# Height_Gauge-2-1.net
KiCad netlist of a schematic drawn in EAGLE
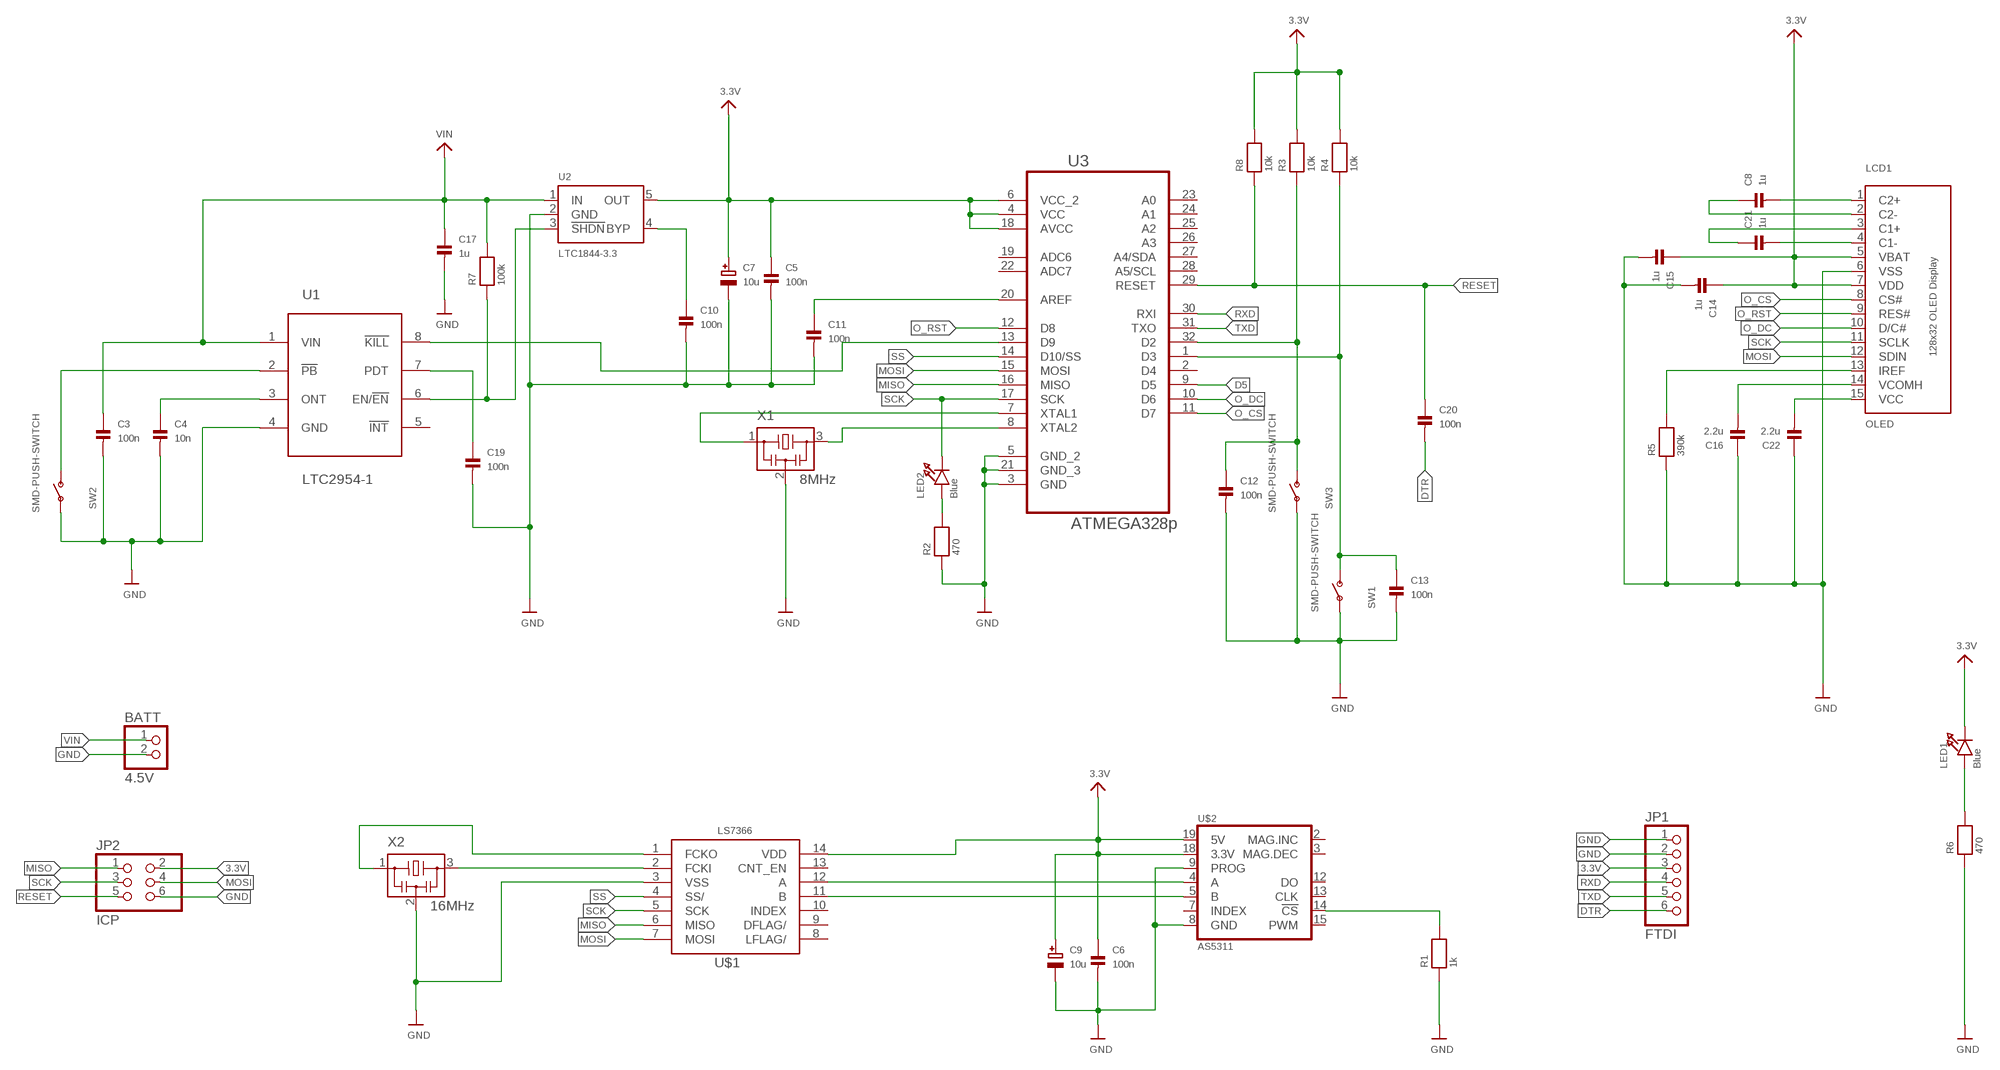
[diagram p0: schematic, sheet 1]

(export (version "E")
  (design (tool "Eeschema 10.0.6"))
  (components
    (comp (ref "BATT")
      (value "4.5V")
      (footprint "eagle-import:1X02")
      (libsource (lib "eagle-import") (part "PINHD-1X2"))
    )
    (comp (ref "C3")
      (value "100n")
      (footprint "eagle-import:0805")
      (libsource (lib "eagle-import") (part "CAP_CERAMIC0805"))
    )
    (comp (ref "C4")
      (value "10n")
      (footprint "eagle-import:0805")
      (libsource (lib "eagle-import") (part "CAP_CERAMIC0805"))
    )
    (comp (ref "C5")
      (value "100n")
      (footprint "eagle-import:0805")
      (libsource (lib "eagle-import") (part "CAP_CERAMIC0805"))
    )
    (comp (ref "C6")
      (value "100n")
      (footprint "eagle-import:0805")
      (libsource (lib "eagle-import") (part "CAP_CERAMIC0805"))
    )
    (comp (ref "C7")
      (value "10u")
      (footprint "eagle-import:EIA3216-18_A-W")
      (libsource (lib "eagle-import") (part "CAP_TANTALUMA/3216_WAVE"))
    )
    (comp (ref "C8")
      (value "1u")
      (footprint "eagle-import:0805")
      (libsource (lib "eagle-import") (part "CAP_CERAMIC0805"))
    )
    (comp (ref "C9")
      (value "10u")
      (footprint "eagle-import:EIA3216-18_A-W")
      (libsource (lib "eagle-import") (part "CAP_TANTALUMA/3216_WAVE"))
    )
    (comp (ref "C10")
      (value "100n")
      (footprint "eagle-import:0805")
      (libsource (lib "eagle-import") (part "CAP_CERAMIC0805"))
    )
    (comp (ref "C11")
      (value "100n")
      (footprint "eagle-import:0805")
      (libsource (lib "eagle-import") (part "CAP_CERAMIC0805"))
    )
    (comp (ref "C12")
      (value "100n")
      (footprint "eagle-import:0805")
      (libsource (lib "eagle-import") (part "CAP_CERAMIC0805"))
    )
    (comp (ref "C13")
      (value "100n")
      (footprint "eagle-import:0805")
      (libsource (lib "eagle-import") (part "CAP_CERAMIC0805"))
    )
    (comp (ref "C14")
      (value "1u")
      (footprint "eagle-import:0805")
      (libsource (lib "eagle-import") (part "CAP_CERAMIC0805"))
    )
    (comp (ref "C15")
      (value "1u")
      (footprint "eagle-import:0805")
      (libsource (lib "eagle-import") (part "CAP_CERAMIC0805"))
    )
    (comp (ref "C16")
      (value "2.2u")
      (footprint "eagle-import:0805")
      (libsource (lib "eagle-import") (part "CAP_CERAMIC0805"))
    )
    (comp (ref "C17")
      (value "1u")
      (footprint "eagle-import:0805")
      (libsource (lib "eagle-import") (part "CAP_CERAMIC0805"))
    )
    (comp (ref "C19")
      (value "100n")
      (footprint "eagle-import:0805")
      (libsource (lib "eagle-import") (part "CAP_CERAMIC0805"))
    )
    (comp (ref "C20")
      (value "100n")
      (footprint "eagle-import:0805")
      (libsource (lib "eagle-import") (part "CAP_CERAMIC0805"))
    )
    (comp (ref "C21")
      (value "1u")
      (footprint "eagle-import:0805")
      (libsource (lib "eagle-import") (part "CAP_CERAMIC0805"))
    )
    (comp (ref "C22")
      (value "2.2u")
      (footprint "eagle-import:0805")
      (libsource (lib "eagle-import") (part "CAP_CERAMIC0805"))
    )
    (comp (ref "JP1")
      (value "FTDI")
      (footprint "eagle-import:1X06-BIG")
      (libsource (lib "eagle-import") (part "PINHD-1X6B"))
    )
    (comp (ref "JP2")
      (value "ICP")
      (footprint "eagle-import:2X03")
      (libsource (lib "eagle-import") (part "PINHD-2X3"))
    )
    (comp (ref "LCD1")
      (value "OLED")
      (footprint "eagle-import:UG-2832HSWEG04_WRAPAROUND")
      (libsource (lib "eagle-import") (part "DISP_OLED_UG-2832HSWEG04WRAPAROUND"))
    )
    (comp (ref "LED1")
      (value "Blue")
      (footprint "eagle-import:CHIPLED_0805")
      (libsource (lib "eagle-import") (part "LED0805"))
    )
    (comp (ref "LED2")
      (value "Blue")
      (footprint "eagle-import:CHIPLED_0805")
      (libsource (lib "eagle-import") (part "LED0805"))
    )
    (comp (ref "R1")
      (value "1k")
      (footprint "eagle-import:0805")
      (libsource (lib "eagle-import") (part "RESISTOR0805"))
    )
    (comp (ref "R2")
      (value "470")
      (footprint "eagle-import:0805")
      (libsource (lib "eagle-import") (part "RESISTOR0805"))
    )
    (comp (ref "R3")
      (value "10k")
      (footprint "eagle-import:0805")
      (libsource (lib "eagle-import") (part "RESISTOR0805"))
    )
    (comp (ref "R4")
      (value "10k")
      (footprint "eagle-import:0805")
      (libsource (lib "eagle-import") (part "RESISTOR0805"))
    )
    (comp (ref "R5")
      (value "390k")
      (footprint "eagle-import:0805")
      (libsource (lib "eagle-import") (part "RESISTOR0805"))
    )
    (comp (ref "R6")
      (value "470")
      (footprint "eagle-import:0805")
      (libsource (lib "eagle-import") (part "RESISTOR0805"))
    )
    (comp (ref "R7")
      (value "100k")
      (footprint "eagle-import:0805")
      (libsource (lib "eagle-import") (part "RESISTOR0805"))
    )
    (comp (ref "R8")
      (value "10k")
      (footprint "eagle-import:0805")
      (libsource (lib "eagle-import") (part "RESISTOR0805"))
    )
    (comp (ref "SW1")
      (value "SMD-PUSH-SWITCH")
      (footprint "eagle-import:PUSH-BUTTON-SMD")
      (libsource (lib "eagle-import") (part "SMD-PUSH-SWITCH"))
    )
    (comp (ref "SW2")
      (value "SMD-PUSH-SWITCH")
      (footprint "eagle-import:PUSH-BUTTON-SMD")
      (libsource (lib "eagle-import") (part "SMD-PUSH-SWITCH"))
    )
    (comp (ref "SW3")
      (value "SMD-PUSH-SWITCH")
      (footprint "eagle-import:PUSH-BUTTON-SMD")
      (libsource (lib "eagle-import") (part "SMD-PUSH-SWITCH"))
    )
    (comp (ref "U$1")
      (value "LS7366")
      (footprint "eagle-import:SO14")
      (libsource (lib "eagle-import") (part "LS7366"))
    )
    (comp (ref "U$2")
      (value "AS5311")
      (footprint "eagle-import:TSSOP.20")
      (libsource (lib "eagle-import") (part "AS5311"))
    )
    (comp (ref "U1")
      (value "LTC2954-1")
      (footprint "eagle-import:TSOT23-8")
      (libsource (lib "eagle-import") (part "LTC2954"))
    )
    (comp (ref "U2")
      (value "LTC1844-3.3")
      (footprint "eagle-import:TSOT23-5")
      (libsource (lib "eagle-import") (part "LTC1844"))
    )
    (comp (ref "U3")
      (value "ATMEGA328p")
      (footprint "eagle-import:TQFP-32")
      (libsource (lib "eagle-import") (part "ATMEGA328P-AU"))
    )
    (comp (ref "X1")
      (value "8MHz")
      (footprint "eagle-import:CSTCE-CRYSTAL-OSC")
      (libsource (lib "eagle-import") (part "CSTCE-CRYSTAL-OSC"))
    )
    (comp (ref "X2")
      (value "16MHz")
      (footprint "eagle-import:CSTCE-CRYSTAL-OSC")
      (libsource (lib "eagle-import") (part "CSTCE-CRYSTAL-OSC"))
    )
  )
  (nets
    (net (code "1") (name "3.3V") (class "Default")
      (node (ref "C14") (pin "1") (pinfunction "P$1_1") (pintype "passive"))
      (node (ref "C15") (pin "1") (pinfunction "P$1_1") (pintype "passive"))
      (node (ref "C5") (pin "1") (pinfunction "P$1_1") (pintype "passive"))
      (node (ref "C6") (pin "1") (pinfunction "P$1_1") (pintype "passive"))
      (node (ref "C7") (pin "+") (pinfunction "+_+") (pintype "passive"))
      (node (ref "C9") (pin "+") (pinfunction "+_+") (pintype "passive"))
      (node (ref "JP1") (pin "3") (pinfunction "3_3") (pintype "passive"))
      (node (ref "JP2") (pin "2") (pinfunction "2_2") (pintype "passive"))
      (node (ref "LCD1") (pin "5") (pinfunction "VBAT_5") (pintype "bidirectional"))
      (node (ref "LCD1") (pin "7") (pinfunction "VDD_7") (pintype "bidirectional"))
      (node (ref "LED1") (pin "C") (pinfunction "C_C") (pintype "passive"))
      (node (ref "R3") (pin "2") (pinfunction "2_2") (pintype "passive"))
      (node (ref "R4") (pin "2") (pinfunction "2_2") (pintype "passive"))
      (node (ref "R8") (pin "2") (pinfunction "2_2") (pintype "passive"))
      (node (ref "U$1") (pin "14") (pinfunction "VDD_14") (pintype "power_in"))
      (node (ref "U$2") (pin "18") (pinfunction "3.3V_18") (pintype "bidirectional"))
      (node (ref "U$2") (pin "19") (pinfunction "5V_19") (pintype "bidirectional"))
      (node (ref "U2") (pin "5") (pinfunction "OUT_5") (pintype "bidirectional"))
      (node (ref "U3") (pin "18") (pinfunction "AVCC_18") (pintype "power_in"))
      (node (ref "U3") (pin "4") (pinfunction "VCC_4") (pintype "power_in"))
      (node (ref "U3") (pin "6") (pinfunction "VCC_2_6") (pintype "power_in"))
    )
    (net (code "2") (name "D5") (class "Default")
      (node (ref "U3") (pin "9") (pinfunction "D5_9") (pintype "bidirectional"))
    )
    (net (code "3") (name "DTR") (class "Default")
      (node (ref "C20") (pin "2") (pinfunction "P$2_2") (pintype "passive"))
      (node (ref "JP1") (pin "6") (pinfunction "6_6") (pintype "passive"))
    )
    (net (code "4") (name "GND") (class "Default")
      (node (ref "BATT") (pin "2") (pinfunction "2_2") (pintype "passive"))
      (node (ref "C10") (pin "2") (pinfunction "P$2_2") (pintype "passive"))
      (node (ref "C11") (pin "2") (pinfunction "P$2_2") (pintype "passive"))
      (node (ref "C12") (pin "2") (pinfunction "P$2_2") (pintype "passive"))
      (node (ref "C13") (pin "2") (pinfunction "P$2_2") (pintype "passive"))
      (node (ref "C14") (pin "2") (pinfunction "P$2_2") (pintype "passive"))
      (node (ref "C15") (pin "2") (pinfunction "P$2_2") (pintype "passive"))
      (node (ref "C16") (pin "1") (pinfunction "P$1_1") (pintype "passive"))
      (node (ref "C17") (pin "2") (pinfunction "P$2_2") (pintype "passive"))
      (node (ref "C19") (pin "2") (pinfunction "P$2_2") (pintype "passive"))
      (node (ref "C22") (pin "1") (pinfunction "P$1_1") (pintype "passive"))
      (node (ref "C3") (pin "2") (pinfunction "P$2_2") (pintype "passive"))
      (node (ref "C4") (pin "2") (pinfunction "P$2_2") (pintype "passive"))
      (node (ref "C5") (pin "2") (pinfunction "P$2_2") (pintype "passive"))
      (node (ref "C6") (pin "2") (pinfunction "P$2_2") (pintype "passive"))
      (node (ref "C7") (pin "-") (pinfunction "-_-") (pintype "passive"))
      (node (ref "C9") (pin "-") (pinfunction "-_-") (pintype "passive"))
      (node (ref "JP1") (pin "1") (pinfunction "1_1") (pintype "passive"))
      (node (ref "JP1") (pin "2") (pinfunction "2_2") (pintype "passive"))
      (node (ref "JP2") (pin "6") (pinfunction "6_6") (pintype "passive"))
      (node (ref "LCD1") (pin "6") (pinfunction "VSS_6") (pintype "bidirectional"))
      (node (ref "R1") (pin "1") (pinfunction "1_1") (pintype "passive"))
      (node (ref "R2") (pin "1") (pinfunction "1_1") (pintype "passive"))
      (node (ref "R5") (pin "1") (pinfunction "1_1") (pintype "passive"))
      (node (ref "R6") (pin "1") (pinfunction "1_1") (pintype "passive"))
      (node (ref "SW1") (pin "P$1") (pinfunction "P_P$1") (pintype "passive"))
      (node (ref "SW2") (pin "P$1") (pinfunction "P_P$1") (pintype "passive"))
      (node (ref "SW3") (pin "P$1") (pinfunction "P_P$1") (pintype "passive"))
      (node (ref "U$1") (pin "3") (pinfunction "VSS_3") (pintype "power_in"))
      (node (ref "U$2") (pin "8") (pinfunction "GND_8") (pintype "bidirectional"))
      (node (ref "U$2") (pin "9") (pinfunction "PROG_9") (pintype "bidirectional"))
      (node (ref "U1") (pin "4") (pinfunction "GND_4") (pintype "bidirectional"))
      (node (ref "U2") (pin "2") (pinfunction "GND_2") (pintype "bidirectional"))
      (node (ref "U3") (pin "21") (pinfunction "GND_3_21") (pintype "passive"))
      (node (ref "U3") (pin "3") (pinfunction "GND_3") (pintype "passive"))
      (node (ref "U3") (pin "5") (pinfunction "GND_2_5") (pintype "passive"))
      (node (ref "X1") (pin "2") (pinfunction "2_2") (pintype "passive"))
      (node (ref "X2") (pin "2") (pinfunction "2_2") (pintype "passive"))
    )
    (net (code "5") (name "MISO") (class "Default")
      (node (ref "JP2") (pin "1") (pinfunction "1_1") (pintype "passive"))
      (node (ref "U$1") (pin "6") (pinfunction "MISO_6") (pintype "output"))
      (node (ref "U3") (pin "16") (pinfunction "MISO_16") (pintype "bidirectional"))
    )
    (net (code "6") (name "MOSI") (class "Default")
      (node (ref "JP2") (pin "4") (pinfunction "4_4") (pintype "passive"))
      (node (ref "LCD1") (pin "12") (pinfunction "SDIN_12") (pintype "bidirectional"))
      (node (ref "U$1") (pin "7") (pinfunction "MOSI_7") (pintype "input"))
      (node (ref "U3") (pin "15") (pinfunction "MOSI_15") (pintype "bidirectional"))
    )
    (net (code "7") (name "Net-(C4-P$1)") (class "Default")
      (node (ref "C4") (pin "1") (pinfunction "P$1_1") (pintype "passive"))
      (node (ref "U1") (pin "3") (pinfunction "ONT_3") (pintype "bidirectional"))
    )
    (net (code "8") (name "Net-(C8-P$1)") (class "Default")
      (node (ref "C8") (pin "1") (pinfunction "P$1_1") (pintype "passive"))
      (node (ref "LCD1") (pin "2") (pinfunction "C2-_2") (pintype "bidirectional"))
    )
    (net (code "9") (name "Net-(C8-P$2)") (class "Default")
      (node (ref "C8") (pin "2") (pinfunction "P$2_2") (pintype "passive"))
      (node (ref "LCD1") (pin "1") (pinfunction "C2+_1") (pintype "bidirectional"))
    )
    (net (code "10") (name "Net-(C10-P$1)") (class "Default")
      (node (ref "C10") (pin "1") (pinfunction "P$1_1") (pintype "passive"))
      (node (ref "U2") (pin "4") (pinfunction "BYP_4") (pintype "bidirectional"))
    )
    (net (code "11") (name "Net-(C11-P$1)") (class "Default")
      (node (ref "C11") (pin "1") (pinfunction "P$1_1") (pintype "passive"))
      (node (ref "U3") (pin "20") (pinfunction "AREF_20") (pintype "input"))
    )
    (net (code "12") (name "Net-(C12-P$1)") (class "Default")
      (node (ref "C12") (pin "1") (pinfunction "P$1_1") (pintype "passive"))
      (node (ref "R3") (pin "1") (pinfunction "1_1") (pintype "passive"))
      (node (ref "SW3") (pin "P$2") (pinfunction "S_P$2") (pintype "passive"))
      (node (ref "U3") (pin "32") (pinfunction "D2_32") (pintype "bidirectional"))
    )
    (net (code "13") (name "Net-(C13-P$1)") (class "Default")
      (node (ref "C13") (pin "1") (pinfunction "P$1_1") (pintype "passive"))
      (node (ref "R4") (pin "1") (pinfunction "1_1") (pintype "passive"))
      (node (ref "SW1") (pin "P$2") (pinfunction "S_P$2") (pintype "passive"))
      (node (ref "U3") (pin "1") (pinfunction "D3_1") (pintype "bidirectional"))
    )
    (net (code "14") (name "Net-(C16-P$2)") (class "Default")
      (node (ref "C16") (pin "2") (pinfunction "P$2_2") (pintype "passive"))
      (node (ref "LCD1") (pin "14") (pinfunction "VCOMH_14") (pintype "bidirectional"))
    )
    (net (code "15") (name "Net-(C19-P$1)") (class "Default")
      (node (ref "C19") (pin "1") (pinfunction "P$1_1") (pintype "passive"))
      (node (ref "U1") (pin "7") (pinfunction "PDT_7") (pintype "bidirectional"))
    )
    (net (code "16") (name "Net-(C21-P$1)") (class "Default")
      (node (ref "C21") (pin "1") (pinfunction "P$1_1") (pintype "passive"))
      (node (ref "LCD1") (pin "3") (pinfunction "C1+_3") (pintype "bidirectional"))
    )
    (net (code "17") (name "Net-(C21-P$2)") (class "Default")
      (node (ref "C21") (pin "2") (pinfunction "P$2_2") (pintype "passive"))
      (node (ref "LCD1") (pin "4") (pinfunction "C1-_4") (pintype "bidirectional"))
    )
    (net (code "18") (name "Net-(C22-P$2)") (class "Default")
      (node (ref "C22") (pin "2") (pinfunction "P$2_2") (pintype "passive"))
      (node (ref "LCD1") (pin "15") (pinfunction "VCC_15") (pintype "bidirectional"))
    )
    (net (code "19") (name "Net-(LCD1-IREF)") (class "Default")
      (node (ref "LCD1") (pin "13") (pinfunction "IREF_13") (pintype "bidirectional"))
      (node (ref "R5") (pin "2") (pinfunction "2_2") (pintype "passive"))
    )
    (net (code "20") (name "Net-(LED1-PadA)") (class "Default")
      (node (ref "LED1") (pin "A") (pinfunction "A_A") (pintype "passive"))
      (node (ref "R6") (pin "2") (pinfunction "2_2") (pintype "passive"))
    )
    (net (code "21") (name "Net-(LED2-PadA)") (class "Default")
      (node (ref "LED2") (pin "A") (pinfunction "A_A") (pintype "passive"))
      (node (ref "R2") (pin "2") (pinfunction "2_2") (pintype "passive"))
    )
    (net (code "22") (name "Net-(SW2-S)") (class "Default")
      (node (ref "SW2") (pin "P$2") (pinfunction "S_P$2") (pintype "passive"))
      (node (ref "U1") (pin "2") (pinfunction "~{PB}_2") (pintype "bidirectional"))
    )
    (net (code "23") (name "Net-(U$1-A)") (class "Default")
      (node (ref "U$1") (pin "12") (pinfunction "A_12") (pintype "bidirectional"))
      (node (ref "U$2") (pin "4") (pinfunction "A_4") (pintype "bidirectional"))
    )
    (net (code "24") (name "Net-(U$1-B)") (class "Default")
      (node (ref "U$1") (pin "11") (pinfunction "B_11") (pintype "bidirectional"))
      (node (ref "U$2") (pin "5") (pinfunction "B_5") (pintype "bidirectional"))
    )
    (net (code "25") (name "Net-(U$1-FCKI)") (class "Default")
      (node (ref "U$1") (pin "2") (pinfunction "FCKI_2") (pintype "bidirectional"))
      (node (ref "X2") (pin "3") (pinfunction "3_3") (pintype "passive"))
    )
    (net (code "26") (name "Net-(U$1-FCKO)") (class "Default")
      (node (ref "U$1") (pin "1") (pinfunction "FCKO_1") (pintype "bidirectional"))
      (node (ref "X2") (pin "1") (pinfunction "1_1") (pintype "passive"))
    )
    (net (code "27") (name "Net-(U$2-~{CS})") (class "Default")
      (node (ref "R1") (pin "2") (pinfunction "2_2") (pintype "passive"))
      (node (ref "U$2") (pin "14") (pinfunction "~{CS}_14") (pintype "bidirectional"))
    )
    (net (code "28") (name "Net-(U1-EN{slash}~{EN})") (class "Default")
      (node (ref "R7") (pin "1") (pinfunction "1_1") (pintype "passive"))
      (node (ref "U1") (pin "6") (pinfunction "EN/~{EN}_6") (pintype "bidirectional"))
      (node (ref "U2") (pin "3") (pinfunction "~{SHDN}_3") (pintype "bidirectional"))
    )
    (net (code "29") (name "Net-(U1-~{KILL})") (class "Default")
      (node (ref "U1") (pin "8") (pinfunction "~{KILL}_8") (pintype "bidirectional"))
      (node (ref "U3") (pin "13") (pinfunction "D9_13") (pintype "bidirectional"))
    )
    (net (code "30") (name "Net-(U3-XTAL1)") (class "Default")
      (node (ref "U3") (pin "7") (pinfunction "XTAL1_7") (pintype "bidirectional"))
      (node (ref "X1") (pin "1") (pinfunction "1_1") (pintype "passive"))
    )
    (net (code "31") (name "Net-(U3-XTAL2)") (class "Default")
      (node (ref "U3") (pin "8") (pinfunction "XTAL2_8") (pintype "bidirectional"))
      (node (ref "X1") (pin "3") (pinfunction "3_3") (pintype "passive"))
    )
    (net (code "32") (name "O_CS") (class "Default")
      (node (ref "LCD1") (pin "8") (pinfunction "CS#_8") (pintype "bidirectional"))
      (node (ref "U3") (pin "11") (pinfunction "D7_11") (pintype "bidirectional"))
    )
    (net (code "33") (name "O_DC") (class "Default")
      (node (ref "LCD1") (pin "10") (pinfunction "D/C#_10") (pintype "bidirectional"))
      (node (ref "U3") (pin "10") (pinfunction "D6_10") (pintype "bidirectional"))
    )
    (net (code "34") (name "O_RST") (class "Default")
      (node (ref "LCD1") (pin "9") (pinfunction "RES#_9") (pintype "bidirectional"))
      (node (ref "U3") (pin "12") (pinfunction "D8_12") (pintype "bidirectional"))
    )
    (net (code "35") (name "RESET") (class "Default")
      (node (ref "C20") (pin "1") (pinfunction "P$1_1") (pintype "passive"))
      (node (ref "JP2") (pin "5") (pinfunction "5_5") (pintype "passive"))
      (node (ref "R8") (pin "1") (pinfunction "1_1") (pintype "passive"))
      (node (ref "U3") (pin "29") (pinfunction "RESET_29") (pintype "bidirectional"))
    )
    (net (code "36") (name "RXD") (class "Default")
      (node (ref "JP1") (pin "4") (pinfunction "4_4") (pintype "passive"))
      (node (ref "U3") (pin "30") (pinfunction "RXI_30") (pintype "bidirectional"))
    )
    (net (code "37") (name "SCK") (class "Default")
      (node (ref "JP2") (pin "3") (pinfunction "3_3") (pintype "passive"))
      (node (ref "LCD1") (pin "11") (pinfunction "SCLK_11") (pintype "bidirectional"))
      (node (ref "LED2") (pin "C") (pinfunction "C_C") (pintype "passive"))
      (node (ref "U$1") (pin "5") (pinfunction "SCK_5") (pintype "bidirectional"))
      (node (ref "U3") (pin "17") (pinfunction "SCK_17") (pintype "bidirectional"))
    )
    (net (code "38") (name "SS") (class "Default")
      (node (ref "U$1") (pin "4") (pinfunction "SS/_4") (pintype "bidirectional"))
      (node (ref "U3") (pin "14") (pinfunction "D10/SS_14") (pintype "bidirectional"))
    )
    (net (code "39") (name "TXD") (class "Default")
      (node (ref "JP1") (pin "5") (pinfunction "5_5") (pintype "passive"))
      (node (ref "U3") (pin "31") (pinfunction "TXO_31") (pintype "bidirectional"))
    )
    (net (code "40") (name "VIN") (class "Default")
      (node (ref "BATT") (pin "1") (pinfunction "1_1") (pintype "passive"))
      (node (ref "C17") (pin "1") (pinfunction "P$1_1") (pintype "passive"))
      (node (ref "C3") (pin "1") (pinfunction "P$1_1") (pintype "passive"))
      (node (ref "R7") (pin "2") (pinfunction "2_2") (pintype "passive"))
      (node (ref "U1") (pin "1") (pinfunction "VIN_1") (pintype "bidirectional"))
      (node (ref "U2") (pin "1") (pinfunction "IN_1") (pintype "bidirectional"))
    )
    (net (code "41") (name "unconnected-(U$1-CNT_EN-Pad13)") (class "Default")
      (node (ref "U$1") (pin "13") (pinfunction "CNT_EN_13") (pintype "bidirectional"))
    )
    (net (code "42") (name "unconnected-(U$1-DFLAG{slash}-Pad9)") (class "Default")
      (node (ref "U$1") (pin "9") (pinfunction "DFLAG/_9") (pintype "output"))
    )
    (net (code "43") (name "unconnected-(U$1-INDEX-Pad10)") (class "Default")
      (node (ref "U$1") (pin "10") (pinfunction "INDEX_10") (pintype "bidirectional"))
    )
    (net (code "44") (name "unconnected-(U$1-LFLAG{slash}-Pad8)") (class "Default")
      (node (ref "U$1") (pin "8") (pinfunction "LFLAG/_8") (pintype "output"))
    )
    (net (code "45") (name "unconnected-(U$2-CLK-Pad13)") (class "Default")
      (node (ref "U$2") (pin "13") (pinfunction "CLK_13") (pintype "bidirectional"))
    )
    (net (code "46") (name "unconnected-(U$2-DO-Pad12)") (class "Default")
      (node (ref "U$2") (pin "12") (pinfunction "DO_12") (pintype "bidirectional"))
    )
    (net (code "47") (name "unconnected-(U$2-INDEX-Pad7)") (class "Default")
      (node (ref "U$2") (pin "7") (pinfunction "INDEX_7") (pintype "bidirectional"))
    )
    (net (code "48") (name "unconnected-(U$2-MAG.DEC-Pad3)") (class "Default")
      (node (ref "U$2") (pin "3") (pinfunction "MAG.DEC_3") (pintype "bidirectional"))
    )
    (net (code "49") (name "unconnected-(U$2-MAG.INC-Pad2)") (class "Default")
      (node (ref "U$2") (pin "2") (pinfunction "MAG.INC_2") (pintype "bidirectional"))
    )
    (net (code "50") (name "unconnected-(U$2-PWM-Pad15)") (class "Default")
      (node (ref "U$2") (pin "15") (pinfunction "PWM_15") (pintype "bidirectional"))
    )
    (net (code "51") (name "unconnected-(U1-~{INT}-Pad5)") (class "Default")
      (node (ref "U1") (pin "5") (pinfunction "~{INT}_5") (pintype "bidirectional"))
    )
    (net (code "52") (name "unconnected-(U3-A0-Pad23)") (class "Default")
      (node (ref "U3") (pin "23") (pinfunction "A0_23") (pintype "bidirectional"))
    )
    (net (code "53") (name "unconnected-(U3-A1-Pad24)") (class "Default")
      (node (ref "U3") (pin "24") (pinfunction "A1_24") (pintype "bidirectional"))
    )
    (net (code "54") (name "unconnected-(U3-A2-Pad25)") (class "Default")
      (node (ref "U3") (pin "25") (pinfunction "A2_25") (pintype "bidirectional"))
    )
    (net (code "55") (name "unconnected-(U3-A3-Pad26)") (class "Default")
      (node (ref "U3") (pin "26") (pinfunction "A3_26") (pintype "bidirectional"))
    )
    (net (code "56") (name "unconnected-(U3-A4{slash}SDA-Pad27)") (class "Default")
      (node (ref "U3") (pin "27") (pinfunction "A4/SDA_27") (pintype "bidirectional"))
    )
    (net (code "57") (name "unconnected-(U3-A5{slash}SCL-Pad28)") (class "Default")
      (node (ref "U3") (pin "28") (pinfunction "A5/SCL_28") (pintype "bidirectional"))
    )
    (net (code "58") (name "unconnected-(U3-ADC6-Pad19)") (class "Default")
      (node (ref "U3") (pin "19") (pinfunction "ADC6_19") (pintype "input"))
    )
    (net (code "59") (name "unconnected-(U3-ADC7-Pad22)") (class "Default")
      (node (ref "U3") (pin "22") (pinfunction "ADC7_22") (pintype "input"))
    )
    (net (code "60") (name "unconnected-(U3-D4-Pad2)") (class "Default")
      (node (ref "U3") (pin "2") (pinfunction "D4_2") (pintype "bidirectional"))
    )
  )
)
